# Eagle_LEDCUBE.net
KiCad netlist of a schematic drawn in EAGLE
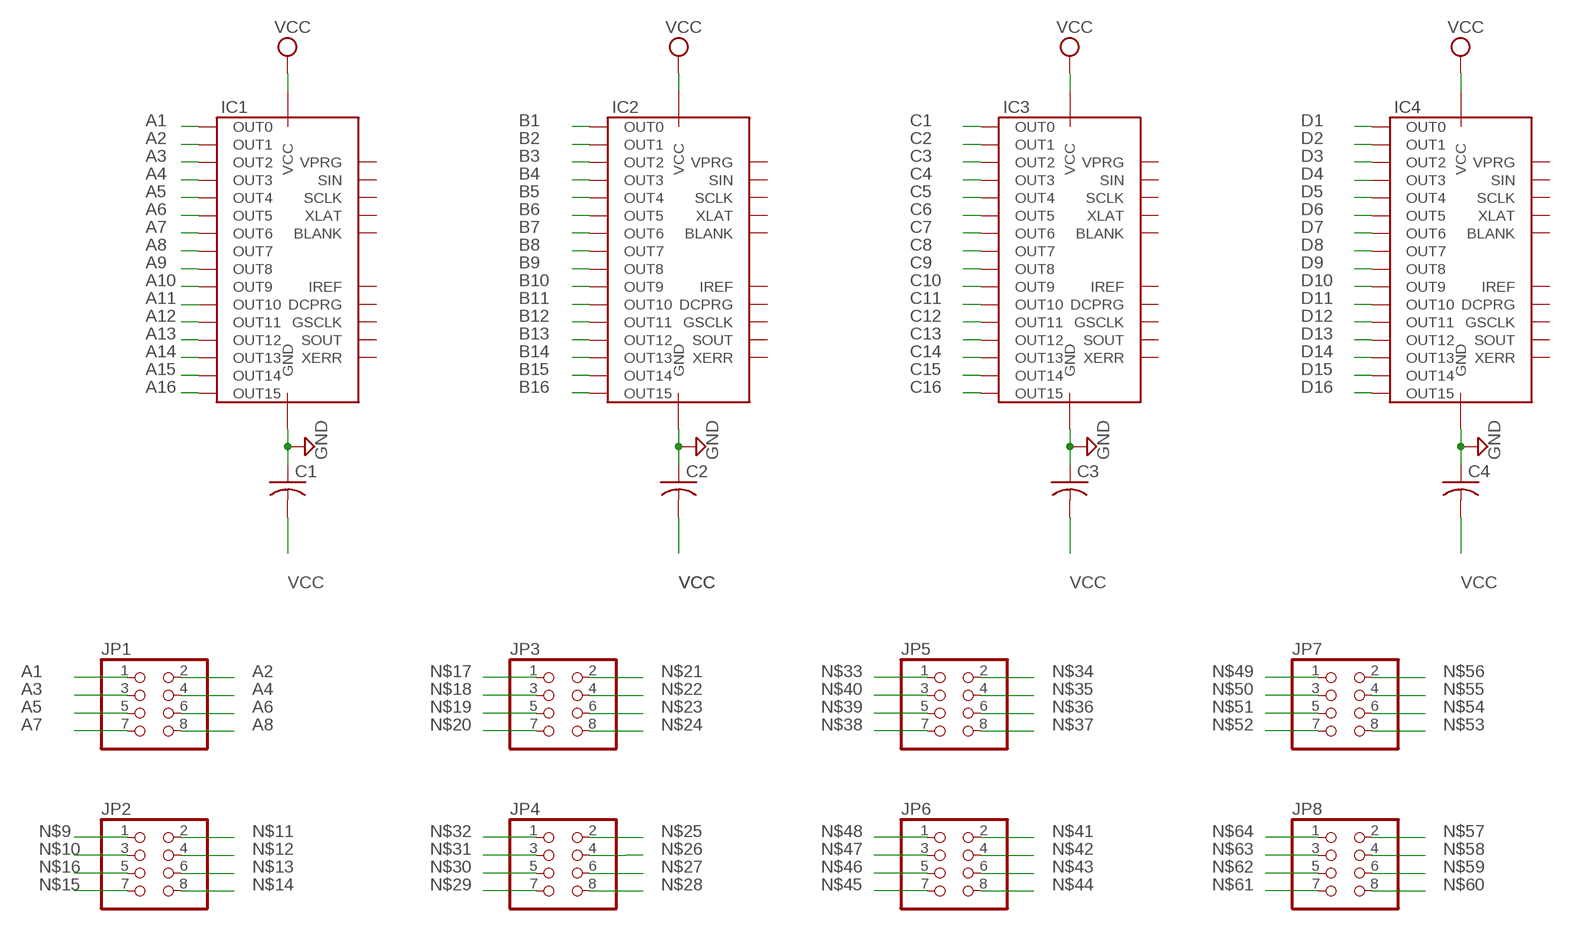
[diagram p0: schematic, sheet 1]

(export (version "E")
  (design (tool "Eeschema 10.0.6"))
  (components
    (comp (ref "C1")
      (value "C-USC0805K")
      (footprint "eagle-import:C0805K")
      (libsource (lib "eagle-import") (part "C-USC0805K"))
    )
    (comp (ref "C2")
      (value "C-USC0805K")
      (footprint "eagle-import:C0805K")
      (libsource (lib "eagle-import") (part "C-USC0805K"))
    )
    (comp (ref "C3")
      (value "C-USC0805K")
      (footprint "eagle-import:C0805K")
      (libsource (lib "eagle-import") (part "C-USC0805K"))
    )
    (comp (ref "C4")
      (value "C-USC0805K")
      (footprint "eagle-import:C0805K")
      (libsource (lib "eagle-import") (part "C-USC0805K"))
    )
    (comp (ref "IC1")
      (value "IC-PACKAGE_DIL28-1")
      (footprint "eagle-import:IC-SSOP28")
      (libsource (lib "eagle-import") (part "IC-PACKAGE_DIL28-1"))
    )
    (comp (ref "IC2")
      (value "IC-PACKAGE_DIL28-1")
      (footprint "eagle-import:IC-SSOP28")
      (libsource (lib "eagle-import") (part "IC-PACKAGE_DIL28-1"))
    )
    (comp (ref "IC3")
      (value "IC-PACKAGE_DIL28-1")
      (footprint "eagle-import:IC-SSOP28")
      (libsource (lib "eagle-import") (part "IC-PACKAGE_DIL28-1"))
    )
    (comp (ref "IC4")
      (value "IC-PACKAGE_DIL28-1")
      (footprint "eagle-import:IC-SSOP28")
      (libsource (lib "eagle-import") (part "IC-PACKAGE_DIL28-1"))
    )
    (comp (ref "JP1")
      (value "PINHD-2X4")
      (footprint "eagle-import:2X04")
      (libsource (lib "eagle-import") (part "PINHD-2X4"))
    )
    (comp (ref "JP2")
      (value "PINHD-2X4")
      (footprint "eagle-import:2X04")
      (libsource (lib "eagle-import") (part "PINHD-2X4"))
    )
    (comp (ref "JP3")
      (value "PINHD-2X4")
      (footprint "eagle-import:2X04")
      (libsource (lib "eagle-import") (part "PINHD-2X4"))
    )
    (comp (ref "JP4")
      (value "PINHD-2X4")
      (footprint "eagle-import:2X04")
      (libsource (lib "eagle-import") (part "PINHD-2X4"))
    )
    (comp (ref "JP5")
      (value "PINHD-2X4")
      (footprint "eagle-import:2X04")
      (libsource (lib "eagle-import") (part "PINHD-2X4"))
    )
    (comp (ref "JP6")
      (value "PINHD-2X4")
      (footprint "eagle-import:2X04")
      (libsource (lib "eagle-import") (part "PINHD-2X4"))
    )
    (comp (ref "JP7")
      (value "PINHD-2X4")
      (footprint "eagle-import:2X04")
      (libsource (lib "eagle-import") (part "PINHD-2X4"))
    )
    (comp (ref "JP8")
      (value "PINHD-2X4")
      (footprint "eagle-import:2X04")
      (libsource (lib "eagle-import") (part "PINHD-2X4"))
    )
  )
  (nets
    (net (code "1") (name "/A1") (class "Default")
      (node (ref "IC1") (pin "7") (pinfunction "OUT0_7") (pintype "open_collector"))
      (node (ref "JP1") (pin "1") (pinfunction "1_1") (pintype "passive"))
    )
    (net (code "2") (name "/A2") (class "Default")
      (node (ref "IC1") (pin "8") (pinfunction "OUT1_8") (pintype "open_collector"))
      (node (ref "JP1") (pin "2") (pinfunction "2_2") (pintype "passive"))
    )
    (net (code "3") (name "/A3") (class "Default")
      (node (ref "IC1") (pin "9") (pinfunction "OUT2_9") (pintype "open_collector"))
      (node (ref "JP1") (pin "3") (pinfunction "3_3") (pintype "passive"))
    )
    (net (code "4") (name "/A4") (class "Default")
      (node (ref "IC1") (pin "10") (pinfunction "OUT3_10") (pintype "open_collector"))
      (node (ref "JP1") (pin "4") (pinfunction "4_4") (pintype "passive"))
    )
    (net (code "5") (name "/A5") (class "Default")
      (node (ref "IC1") (pin "11") (pinfunction "OUT4_11") (pintype "open_collector"))
      (node (ref "JP1") (pin "5") (pinfunction "5_5") (pintype "passive"))
    )
    (net (code "6") (name "/A6") (class "Default")
      (node (ref "IC1") (pin "12") (pinfunction "OUT5_12") (pintype "open_collector"))
      (node (ref "JP1") (pin "6") (pinfunction "6_6") (pintype "passive"))
    )
    (net (code "7") (name "/A7") (class "Default")
      (node (ref "IC1") (pin "13") (pinfunction "OUT6_13") (pintype "open_collector"))
      (node (ref "JP1") (pin "7") (pinfunction "7_7") (pintype "passive"))
    )
    (net (code "8") (name "/A8") (class "Default")
      (node (ref "IC1") (pin "14") (pinfunction "OUT7_14") (pintype "open_collector"))
      (node (ref "JP1") (pin "8") (pinfunction "8_8") (pintype "passive"))
    )
    (net (code "9") (name "/A9") (class "Default")
      (node (ref "IC1") (pin "15") (pinfunction "OUT8_15") (pintype "open_collector"))
    )
    (net (code "10") (name "/A10") (class "Default")
      (node (ref "IC1") (pin "16") (pinfunction "OUT9_16") (pintype "open_collector"))
    )
    (net (code "11") (name "/A11") (class "Default")
      (node (ref "IC1") (pin "17") (pinfunction "OUT10_17") (pintype "open_collector"))
    )
    (net (code "12") (name "/A12") (class "Default")
      (node (ref "IC1") (pin "18") (pinfunction "OUT11_18") (pintype "open_collector"))
    )
    (net (code "13") (name "/A13") (class "Default")
      (node (ref "IC1") (pin "19") (pinfunction "OUT12_19") (pintype "open_collector"))
    )
    (net (code "14") (name "/A14") (class "Default")
      (node (ref "IC1") (pin "20") (pinfunction "OUT13_20") (pintype "open_collector"))
    )
    (net (code "15") (name "/A15") (class "Default")
      (node (ref "IC1") (pin "21") (pinfunction "OUT14_21") (pintype "open_collector"))
    )
    (net (code "16") (name "/A16") (class "Default")
      (node (ref "IC1") (pin "22") (pinfunction "OUT15_22") (pintype "open_collector"))
    )
    (net (code "17") (name "/B1") (class "Default")
      (node (ref "IC2") (pin "7") (pinfunction "OUT0_7") (pintype "open_collector"))
    )
    (net (code "18") (name "/B2") (class "Default")
      (node (ref "IC2") (pin "8") (pinfunction "OUT1_8") (pintype "open_collector"))
    )
    (net (code "19") (name "/B3") (class "Default")
      (node (ref "IC2") (pin "9") (pinfunction "OUT2_9") (pintype "open_collector"))
    )
    (net (code "20") (name "/B4") (class "Default")
      (node (ref "IC2") (pin "10") (pinfunction "OUT3_10") (pintype "open_collector"))
    )
    (net (code "21") (name "/B5") (class "Default")
      (node (ref "IC2") (pin "11") (pinfunction "OUT4_11") (pintype "open_collector"))
    )
    (net (code "22") (name "/B6") (class "Default")
      (node (ref "IC2") (pin "12") (pinfunction "OUT5_12") (pintype "open_collector"))
    )
    (net (code "23") (name "/B7") (class "Default")
      (node (ref "IC2") (pin "13") (pinfunction "OUT6_13") (pintype "open_collector"))
    )
    (net (code "24") (name "/B8") (class "Default")
      (node (ref "IC2") (pin "14") (pinfunction "OUT7_14") (pintype "open_collector"))
    )
    (net (code "25") (name "/B9") (class "Default")
      (node (ref "IC2") (pin "15") (pinfunction "OUT8_15") (pintype "open_collector"))
    )
    (net (code "26") (name "/B10") (class "Default")
      (node (ref "IC2") (pin "16") (pinfunction "OUT9_16") (pintype "open_collector"))
    )
    (net (code "27") (name "/B11") (class "Default")
      (node (ref "IC2") (pin "17") (pinfunction "OUT10_17") (pintype "open_collector"))
    )
    (net (code "28") (name "/B12") (class "Default")
      (node (ref "IC2") (pin "18") (pinfunction "OUT11_18") (pintype "open_collector"))
    )
    (net (code "29") (name "/B13") (class "Default")
      (node (ref "IC2") (pin "19") (pinfunction "OUT12_19") (pintype "open_collector"))
    )
    (net (code "30") (name "/B14") (class "Default")
      (node (ref "IC2") (pin "20") (pinfunction "OUT13_20") (pintype "open_collector"))
    )
    (net (code "31") (name "/B15") (class "Default")
      (node (ref "IC2") (pin "21") (pinfunction "OUT14_21") (pintype "open_collector"))
    )
    (net (code "32") (name "/B16") (class "Default")
      (node (ref "IC2") (pin "22") (pinfunction "OUT15_22") (pintype "open_collector"))
    )
    (net (code "33") (name "/C1") (class "Default")
      (node (ref "IC3") (pin "7") (pinfunction "OUT0_7") (pintype "open_collector"))
    )
    (net (code "34") (name "/C2") (class "Default")
      (node (ref "IC3") (pin "8") (pinfunction "OUT1_8") (pintype "open_collector"))
    )
    (net (code "35") (name "/C3") (class "Default")
      (node (ref "IC3") (pin "9") (pinfunction "OUT2_9") (pintype "open_collector"))
    )
    (net (code "36") (name "/C4") (class "Default")
      (node (ref "IC3") (pin "10") (pinfunction "OUT3_10") (pintype "open_collector"))
    )
    (net (code "37") (name "/C5") (class "Default")
      (node (ref "IC3") (pin "11") (pinfunction "OUT4_11") (pintype "open_collector"))
    )
    (net (code "38") (name "/C6") (class "Default")
      (node (ref "IC3") (pin "12") (pinfunction "OUT5_12") (pintype "open_collector"))
    )
    (net (code "39") (name "/C7") (class "Default")
      (node (ref "IC3") (pin "13") (pinfunction "OUT6_13") (pintype "open_collector"))
    )
    (net (code "40") (name "/C8") (class "Default")
      (node (ref "IC3") (pin "14") (pinfunction "OUT7_14") (pintype "open_collector"))
    )
    (net (code "41") (name "/C9") (class "Default")
      (node (ref "IC3") (pin "15") (pinfunction "OUT8_15") (pintype "open_collector"))
    )
    (net (code "42") (name "/C10") (class "Default")
      (node (ref "IC3") (pin "16") (pinfunction "OUT9_16") (pintype "open_collector"))
    )
    (net (code "43") (name "/C11") (class "Default")
      (node (ref "IC3") (pin "17") (pinfunction "OUT10_17") (pintype "open_collector"))
    )
    (net (code "44") (name "/C12") (class "Default")
      (node (ref "IC3") (pin "18") (pinfunction "OUT11_18") (pintype "open_collector"))
    )
    (net (code "45") (name "/C13") (class "Default")
      (node (ref "IC3") (pin "19") (pinfunction "OUT12_19") (pintype "open_collector"))
    )
    (net (code "46") (name "/C14") (class "Default")
      (node (ref "IC3") (pin "20") (pinfunction "OUT13_20") (pintype "open_collector"))
    )
    (net (code "47") (name "/C15") (class "Default")
      (node (ref "IC3") (pin "21") (pinfunction "OUT14_21") (pintype "open_collector"))
    )
    (net (code "48") (name "/C16") (class "Default")
      (node (ref "IC3") (pin "22") (pinfunction "OUT15_22") (pintype "open_collector"))
    )
    (net (code "49") (name "/D1") (class "Default")
      (node (ref "IC4") (pin "7") (pinfunction "OUT0_7") (pintype "open_collector"))
    )
    (net (code "50") (name "/D2") (class "Default")
      (node (ref "IC4") (pin "8") (pinfunction "OUT1_8") (pintype "open_collector"))
    )
    (net (code "51") (name "/D3") (class "Default")
      (node (ref "IC4") (pin "9") (pinfunction "OUT2_9") (pintype "open_collector"))
    )
    (net (code "52") (name "/D4") (class "Default")
      (node (ref "IC4") (pin "10") (pinfunction "OUT3_10") (pintype "open_collector"))
    )
    (net (code "53") (name "/D5") (class "Default")
      (node (ref "IC4") (pin "11") (pinfunction "OUT4_11") (pintype "open_collector"))
    )
    (net (code "54") (name "/D6") (class "Default")
      (node (ref "IC4") (pin "12") (pinfunction "OUT5_12") (pintype "open_collector"))
    )
    (net (code "55") (name "/D7") (class "Default")
      (node (ref "IC4") (pin "13") (pinfunction "OUT6_13") (pintype "open_collector"))
    )
    (net (code "56") (name "/D8") (class "Default")
      (node (ref "IC4") (pin "14") (pinfunction "OUT7_14") (pintype "open_collector"))
    )
    (net (code "57") (name "/D9") (class "Default")
      (node (ref "IC4") (pin "15") (pinfunction "OUT8_15") (pintype "open_collector"))
    )
    (net (code "58") (name "/D10") (class "Default")
      (node (ref "IC4") (pin "16") (pinfunction "OUT9_16") (pintype "open_collector"))
    )
    (net (code "59") (name "/D11") (class "Default")
      (node (ref "IC4") (pin "17") (pinfunction "OUT10_17") (pintype "open_collector"))
    )
    (net (code "60") (name "/D12") (class "Default")
      (node (ref "IC4") (pin "18") (pinfunction "OUT11_18") (pintype "open_collector"))
    )
    (net (code "61") (name "/D13") (class "Default")
      (node (ref "IC4") (pin "19") (pinfunction "OUT12_19") (pintype "open_collector"))
    )
    (net (code "62") (name "/D14") (class "Default")
      (node (ref "IC4") (pin "20") (pinfunction "OUT13_20") (pintype "open_collector"))
    )
    (net (code "63") (name "/D15") (class "Default")
      (node (ref "IC4") (pin "21") (pinfunction "OUT14_21") (pintype "open_collector"))
    )
    (net (code "64") (name "/D16") (class "Default")
      (node (ref "IC4") (pin "22") (pinfunction "OUT15_22") (pintype "open_collector"))
    )
    (net (code "65") (name "/N$9") (class "Default")
      (node (ref "JP2") (pin "1") (pinfunction "1_1") (pintype "passive"))
    )
    (net (code "66") (name "/N$10") (class "Default")
      (node (ref "JP2") (pin "3") (pinfunction "3_3") (pintype "passive"))
    )
    (net (code "67") (name "/N$11") (class "Default")
      (node (ref "JP2") (pin "2") (pinfunction "2_2") (pintype "passive"))
    )
    (net (code "68") (name "/N$12") (class "Default")
      (node (ref "JP2") (pin "4") (pinfunction "4_4") (pintype "passive"))
    )
    (net (code "69") (name "/N$13") (class "Default")
      (node (ref "JP2") (pin "6") (pinfunction "6_6") (pintype "passive"))
    )
    (net (code "70") (name "/N$14") (class "Default")
      (node (ref "JP2") (pin "8") (pinfunction "8_8") (pintype "passive"))
    )
    (net (code "71") (name "/N$15") (class "Default")
      (node (ref "JP2") (pin "7") (pinfunction "7_7") (pintype "passive"))
    )
    (net (code "72") (name "/N$16") (class "Default")
      (node (ref "JP2") (pin "5") (pinfunction "5_5") (pintype "passive"))
    )
    (net (code "73") (name "/N$17") (class "Default")
      (node (ref "JP3") (pin "1") (pinfunction "1_1") (pintype "passive"))
    )
    (net (code "74") (name "/N$18") (class "Default")
      (node (ref "JP3") (pin "3") (pinfunction "3_3") (pintype "passive"))
    )
    (net (code "75") (name "/N$19") (class "Default")
      (node (ref "JP3") (pin "5") (pinfunction "5_5") (pintype "passive"))
    )
    (net (code "76") (name "/N$20") (class "Default")
      (node (ref "JP3") (pin "7") (pinfunction "7_7") (pintype "passive"))
    )
    (net (code "77") (name "/N$21") (class "Default")
      (node (ref "JP3") (pin "2") (pinfunction "2_2") (pintype "passive"))
    )
    (net (code "78") (name "/N$22") (class "Default")
      (node (ref "JP3") (pin "4") (pinfunction "4_4") (pintype "passive"))
    )
    (net (code "79") (name "/N$23") (class "Default")
      (node (ref "JP3") (pin "6") (pinfunction "6_6") (pintype "passive"))
    )
    (net (code "80") (name "/N$24") (class "Default")
      (node (ref "JP3") (pin "8") (pinfunction "8_8") (pintype "passive"))
    )
    (net (code "81") (name "/N$25") (class "Default")
      (node (ref "JP4") (pin "2") (pinfunction "2_2") (pintype "passive"))
    )
    (net (code "82") (name "/N$26") (class "Default")
      (node (ref "JP4") (pin "4") (pinfunction "4_4") (pintype "passive"))
    )
    (net (code "83") (name "/N$27") (class "Default")
      (node (ref "JP4") (pin "6") (pinfunction "6_6") (pintype "passive"))
    )
    (net (code "84") (name "/N$28") (class "Default")
      (node (ref "JP4") (pin "8") (pinfunction "8_8") (pintype "passive"))
    )
    (net (code "85") (name "/N$29") (class "Default")
      (node (ref "JP4") (pin "7") (pinfunction "7_7") (pintype "passive"))
    )
    (net (code "86") (name "/N$30") (class "Default")
      (node (ref "JP4") (pin "5") (pinfunction "5_5") (pintype "passive"))
    )
    (net (code "87") (name "/N$31") (class "Default")
      (node (ref "JP4") (pin "3") (pinfunction "3_3") (pintype "passive"))
    )
    (net (code "88") (name "/N$32") (class "Default")
      (node (ref "JP4") (pin "1") (pinfunction "1_1") (pintype "passive"))
    )
    (net (code "89") (name "/N$33") (class "Default")
      (node (ref "JP5") (pin "1") (pinfunction "1_1") (pintype "passive"))
    )
    (net (code "90") (name "/N$34") (class "Default")
      (node (ref "JP5") (pin "2") (pinfunction "2_2") (pintype "passive"))
    )
    (net (code "91") (name "/N$35") (class "Default")
      (node (ref "JP5") (pin "4") (pinfunction "4_4") (pintype "passive"))
    )
    (net (code "92") (name "/N$36") (class "Default")
      (node (ref "JP5") (pin "6") (pinfunction "6_6") (pintype "passive"))
    )
    (net (code "93") (name "/N$37") (class "Default")
      (node (ref "JP5") (pin "8") (pinfunction "8_8") (pintype "passive"))
    )
    (net (code "94") (name "/N$38") (class "Default")
      (node (ref "JP5") (pin "7") (pinfunction "7_7") (pintype "passive"))
    )
    (net (code "95") (name "/N$39") (class "Default")
      (node (ref "JP5") (pin "5") (pinfunction "5_5") (pintype "passive"))
    )
    (net (code "96") (name "/N$40") (class "Default")
      (node (ref "JP5") (pin "3") (pinfunction "3_3") (pintype "passive"))
    )
    (net (code "97") (name "/N$41") (class "Default")
      (node (ref "JP6") (pin "2") (pinfunction "2_2") (pintype "passive"))
    )
    (net (code "98") (name "/N$42") (class "Default")
      (node (ref "JP6") (pin "4") (pinfunction "4_4") (pintype "passive"))
    )
    (net (code "99") (name "/N$43") (class "Default")
      (node (ref "JP6") (pin "6") (pinfunction "6_6") (pintype "passive"))
    )
    (net (code "100") (name "/N$44") (class "Default")
      (node (ref "JP6") (pin "8") (pinfunction "8_8") (pintype "passive"))
    )
    (net (code "101") (name "/N$45") (class "Default")
      (node (ref "JP6") (pin "7") (pinfunction "7_7") (pintype "passive"))
    )
    (net (code "102") (name "/N$46") (class "Default")
      (node (ref "JP6") (pin "5") (pinfunction "5_5") (pintype "passive"))
    )
    (net (code "103") (name "/N$47") (class "Default")
      (node (ref "JP6") (pin "3") (pinfunction "3_3") (pintype "passive"))
    )
    (net (code "104") (name "/N$48") (class "Default")
      (node (ref "JP6") (pin "1") (pinfunction "1_1") (pintype "passive"))
    )
    (net (code "105") (name "/N$49") (class "Default")
      (node (ref "JP7") (pin "1") (pinfunction "1_1") (pintype "passive"))
    )
    (net (code "106") (name "/N$50") (class "Default")
      (node (ref "JP7") (pin "3") (pinfunction "3_3") (pintype "passive"))
    )
    (net (code "107") (name "/N$51") (class "Default")
      (node (ref "JP7") (pin "5") (pinfunction "5_5") (pintype "passive"))
    )
    (net (code "108") (name "/N$52") (class "Default")
      (node (ref "JP7") (pin "7") (pinfunction "7_7") (pintype "passive"))
    )
    (net (code "109") (name "/N$53") (class "Default")
      (node (ref "JP7") (pin "8") (pinfunction "8_8") (pintype "passive"))
    )
    (net (code "110") (name "/N$54") (class "Default")
      (node (ref "JP7") (pin "6") (pinfunction "6_6") (pintype "passive"))
    )
    (net (code "111") (name "/N$55") (class "Default")
      (node (ref "JP7") (pin "4") (pinfunction "4_4") (pintype "passive"))
    )
    (net (code "112") (name "/N$56") (class "Default")
      (node (ref "JP7") (pin "2") (pinfunction "2_2") (pintype "passive"))
    )
    (net (code "113") (name "/N$57") (class "Default")
      (node (ref "JP8") (pin "2") (pinfunction "2_2") (pintype "passive"))
    )
    (net (code "114") (name "/N$58") (class "Default")
      (node (ref "JP8") (pin "4") (pinfunction "4_4") (pintype "passive"))
    )
    (net (code "115") (name "/N$59") (class "Default")
      (node (ref "JP8") (pin "6") (pinfunction "6_6") (pintype "passive"))
    )
    (net (code "116") (name "/N$60") (class "Default")
      (node (ref "JP8") (pin "8") (pinfunction "8_8") (pintype "passive"))
    )
    (net (code "117") (name "/N$61") (class "Default")
      (node (ref "JP8") (pin "7") (pinfunction "7_7") (pintype "passive"))
    )
    (net (code "118") (name "/N$62") (class "Default")
      (node (ref "JP8") (pin "5") (pinfunction "5_5") (pintype "passive"))
    )
    (net (code "119") (name "/N$63") (class "Default")
      (node (ref "JP8") (pin "3") (pinfunction "3_3") (pintype "passive"))
    )
    (net (code "120") (name "/N$64") (class "Default")
      (node (ref "JP8") (pin "1") (pinfunction "1_1") (pintype "passive"))
    )
    (net (code "121") (name "GND") (class "Default")
      (node (ref "C1") (pin "1") (pinfunction "1_1") (pintype "passive"))
      (node (ref "C2") (pin "1") (pinfunction "1_1") (pintype "passive"))
      (node (ref "C3") (pin "1") (pinfunction "1_1") (pintype "passive"))
      (node (ref "C4") (pin "1") (pinfunction "1_1") (pintype "passive"))
      (node (ref "IC1") (pin "1") (pinfunction "GND_1") (pintype "power_in"))
      (node (ref "IC2") (pin "1") (pinfunction "GND_1") (pintype "power_in"))
      (node (ref "IC3") (pin "1") (pinfunction "GND_1") (pintype "power_in"))
      (node (ref "IC4") (pin "1") (pinfunction "GND_1") (pintype "power_in"))
    )
    (net (code "122") (name "VCC") (class "Default")
      (node (ref "C1") (pin "2") (pinfunction "2_2") (pintype "passive"))
      (node (ref "C2") (pin "2") (pinfunction "2_2") (pintype "passive"))
      (node (ref "C3") (pin "2") (pinfunction "2_2") (pintype "passive"))
      (node (ref "C4") (pin "2") (pinfunction "2_2") (pintype "passive"))
      (node (ref "IC1") (pin "28") (pinfunction "VCC_28") (pintype "power_in"))
      (node (ref "IC2") (pin "28") (pinfunction "VCC_28") (pintype "power_in"))
      (node (ref "IC3") (pin "28") (pinfunction "VCC_28") (pintype "power_in"))
      (node (ref "IC4") (pin "28") (pinfunction "VCC_28") (pintype "power_in"))
    )
    (net (code "123") (name "unconnected-(IC1-BLANK-Pad2)") (class "Default")
      (node (ref "IC1") (pin "2") (pinfunction "BLANK_2") (pintype "input"))
    )
    (net (code "124") (name "unconnected-(IC1-DCPRG-Pad26)") (class "Default")
      (node (ref "IC1") (pin "26") (pinfunction "DCPRG_26") (pintype "input"))
    )
    (net (code "125") (name "unconnected-(IC1-GSCLK-Pad25)") (class "Default")
      (node (ref "IC1") (pin "25") (pinfunction "GSCLK_25") (pintype "input"))
    )
    (net (code "126") (name "unconnected-(IC1-IREF-Pad27)") (class "Default")
      (node (ref "IC1") (pin "27") (pinfunction "IREF_27") (pintype "passive"))
    )
    (net (code "127") (name "unconnected-(IC1-SCLK-Pad4)") (class "Default")
      (node (ref "IC1") (pin "4") (pinfunction "SCLK_4") (pintype "input"))
    )
    (net (code "128") (name "unconnected-(IC1-SIN-Pad5)") (class "Default")
      (node (ref "IC1") (pin "5") (pinfunction "SIN_5") (pintype "input"))
    )
    (net (code "129") (name "unconnected-(IC1-SOUT-Pad24)") (class "Default")
      (node (ref "IC1") (pin "24") (pinfunction "SOUT_24") (pintype "output"))
    )
    (net (code "130") (name "unconnected-(IC1-VPRG-Pad6)") (class "Default")
      (node (ref "IC1") (pin "6") (pinfunction "VPRG_6") (pintype "input"))
    )
    (net (code "131") (name "unconnected-(IC1-XERR-Pad23)") (class "Default")
      (node (ref "IC1") (pin "23") (pinfunction "XERR_23") (pintype "open_collector"))
    )
    (net (code "132") (name "unconnected-(IC1-XLAT-Pad3)") (class "Default")
      (node (ref "IC1") (pin "3") (pinfunction "XLAT_3") (pintype "input"))
    )
    (net (code "133") (name "unconnected-(IC2-BLANK-Pad2)") (class "Default")
      (node (ref "IC2") (pin "2") (pinfunction "BLANK_2") (pintype "input"))
    )
    (net (code "134") (name "unconnected-(IC2-DCPRG-Pad26)") (class "Default")
      (node (ref "IC2") (pin "26") (pinfunction "DCPRG_26") (pintype "input"))
    )
    (net (code "135") (name "unconnected-(IC2-GSCLK-Pad25)") (class "Default")
      (node (ref "IC2") (pin "25") (pinfunction "GSCLK_25") (pintype "input"))
    )
    (net (code "136") (name "unconnected-(IC2-IREF-Pad27)") (class "Default")
      (node (ref "IC2") (pin "27") (pinfunction "IREF_27") (pintype "passive"))
    )
    (net (code "137") (name "unconnected-(IC2-SCLK-Pad4)") (class "Default")
      (node (ref "IC2") (pin "4") (pinfunction "SCLK_4") (pintype "input"))
    )
    (net (code "138") (name "unconnected-(IC2-SIN-Pad5)") (class "Default")
      (node (ref "IC2") (pin "5") (pinfunction "SIN_5") (pintype "input"))
    )
    (net (code "139") (name "unconnected-(IC2-SOUT-Pad24)") (class "Default")
      (node (ref "IC2") (pin "24") (pinfunction "SOUT_24") (pintype "output"))
    )
    (net (code "140") (name "unconnected-(IC2-VPRG-Pad6)") (class "Default")
      (node (ref "IC2") (pin "6") (pinfunction "VPRG_6") (pintype "input"))
    )
    (net (code "141") (name "unconnected-(IC2-XERR-Pad23)") (class "Default")
      (node (ref "IC2") (pin "23") (pinfunction "XERR_23") (pintype "open_collector"))
    )
    (net (code "142") (name "unconnected-(IC2-XLAT-Pad3)") (class "Default")
      (node (ref "IC2") (pin "3") (pinfunction "XLAT_3") (pintype "input"))
    )
    (net (code "143") (name "unconnected-(IC3-BLANK-Pad2)") (class "Default")
      (node (ref "IC3") (pin "2") (pinfunction "BLANK_2") (pintype "input"))
    )
    (net (code "144") (name "unconnected-(IC3-DCPRG-Pad26)") (class "Default")
      (node (ref "IC3") (pin "26") (pinfunction "DCPRG_26") (pintype "input"))
    )
    (net (code "145") (name "unconnected-(IC3-GSCLK-Pad25)") (class "Default")
      (node (ref "IC3") (pin "25") (pinfunction "GSCLK_25") (pintype "input"))
    )
    (net (code "146") (name "unconnected-(IC3-IREF-Pad27)") (class "Default")
      (node (ref "IC3") (pin "27") (pinfunction "IREF_27") (pintype "passive"))
    )
    (net (code "147") (name "unconnected-(IC3-SCLK-Pad4)") (class "Default")
      (node (ref "IC3") (pin "4") (pinfunction "SCLK_4") (pintype "input"))
    )
    (net (code "148") (name "unconnected-(IC3-SIN-Pad5)") (class "Default")
      (node (ref "IC3") (pin "5") (pinfunction "SIN_5") (pintype "input"))
    )
    (net (code "149") (name "unconnected-(IC3-SOUT-Pad24)") (class "Default")
      (node (ref "IC3") (pin "24") (pinfunction "SOUT_24") (pintype "output"))
    )
    (net (code "150") (name "unconnected-(IC3-VPRG-Pad6)") (class "Default")
      (node (ref "IC3") (pin "6") (pinfunction "VPRG_6") (pintype "input"))
    )
    (net (code "151") (name "unconnected-(IC3-XERR-Pad23)") (class "Default")
      (node (ref "IC3") (pin "23") (pinfunction "XERR_23") (pintype "open_collector"))
    )
    (net (code "152") (name "unconnected-(IC3-XLAT-Pad3)") (class "Default")
      (node (ref "IC3") (pin "3") (pinfunction "XLAT_3") (pintype "input"))
    )
    (net (code "153") (name "unconnected-(IC4-BLANK-Pad2)") (class "Default")
      (node (ref "IC4") (pin "2") (pinfunction "BLANK_2") (pintype "input"))
    )
    (net (code "154") (name "unconnected-(IC4-DCPRG-Pad26)") (class "Default")
      (node (ref "IC4") (pin "26") (pinfunction "DCPRG_26") (pintype "input"))
    )
    (net (code "155") (name "unconnected-(IC4-GSCLK-Pad25)") (class "Default")
      (node (ref "IC4") (pin "25") (pinfunction "GSCLK_25") (pintype "input"))
    )
    (net (code "156") (name "unconnected-(IC4-IREF-Pad27)") (class "Default")
      (node (ref "IC4") (pin "27") (pinfunction "IREF_27") (pintype "passive"))
    )
    (net (code "157") (name "unconnected-(IC4-SCLK-Pad4)") (class "Default")
      (node (ref "IC4") (pin "4") (pinfunction "SCLK_4") (pintype "input"))
    )
    (net (code "158") (name "unconnected-(IC4-SIN-Pad5)") (class "Default")
      (node (ref "IC4") (pin "5") (pinfunction "SIN_5") (pintype "input"))
    )
    (net (code "159") (name "unconnected-(IC4-SOUT-Pad24)") (class "Default")
      (node (ref "IC4") (pin "24") (pinfunction "SOUT_24") (pintype "output"))
    )
    (net (code "160") (name "unconnected-(IC4-VPRG-Pad6)") (class "Default")
      (node (ref "IC4") (pin "6") (pinfunction "VPRG_6") (pintype "input"))
    )
    (net (code "161") (name "unconnected-(IC4-XERR-Pad23)") (class "Default")
      (node (ref "IC4") (pin "23") (pinfunction "XERR_23") (pintype "open_collector"))
    )
    (net (code "162") (name "unconnected-(IC4-XLAT-Pad3)") (class "Default")
      (node (ref "IC4") (pin "3") (pinfunction "XLAT_3") (pintype "input"))
    )
  )
)
